# main.net
KiCad netlist of a schematic drawn in Altium Designer
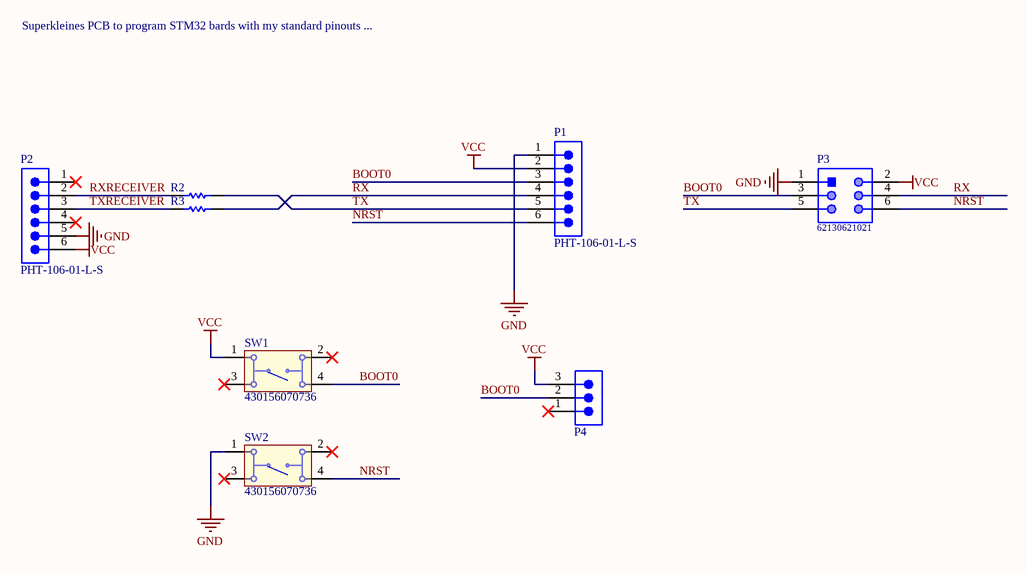
[diagram p0: main.SchDoc]

(export (version "E")
  (design (tool "Eeschema 10.0.6"))
  (components
    (comp (ref "P1")
      (value "PHT-106-01-L-S")
      (footprint "SMTC-PHT-106-01-X-S")
      (description "Press Fit Header, Through-hole, Vertical, -55 to 125 degC, 2.54 mm Pitch, 6-Pin, Male, RoHS")
      (fields (field (name "MANUFACTURER") "Samtec"))
      (libsource (lib "Altium Content Vault") (part "SMTC-PHT-106-01-X-S"))
    )
    (comp (ref "P2")
      (value "PHT-106-01-L-S")
      (footprint "SMTC-PHT-106-01-X-S")
      (description "Press Fit Header, Through-hole, Vertical, -55 to 125 degC, 2.54 mm Pitch, 6-Pin, Male, RoHS")
      (fields (field (name "MANUFACTURER") "Samtec"))
      (libsource (lib "Altium Content Vault") (part "SMTC-PHT-106-01-X-S"))
    )
    (comp (ref "P3")
      (value "62130621021")
      (footprint "62130621021")
      (description "SMT Vertical Pin Header WR-PHD, Pitch 1.27 mm, Dual Row, 6 pins")
      (fields (field (name "MANUFACTURER") "Wurth Elektronik") (field (name "PUBLISHER") "WurthElektronik"))
      (libsource (lib "Altium Content Vault") (part "WE-CN-2P-M-R6"))
    )
    (comp (ref "P4")
      (value "TSW-103-07-F-S")
      (footprint "SMTC-TSW-103-07-X-S")
      (fields (field (name "MANUFACTURER") "Samtec"))
      (libsource (lib "Altium Content Vault") (part "SMTC-TSW-103-X-X-S-X"))
    )
    (comp (ref "R2")
      (value "0")
      (footprint "RESC0805(2012)_L")
      (fields (field (name "TOLERANCE") "1 %") (field (name "POWER") "0.125 W"))
      (libsource (lib "Altium Content Vault") (part "RES"))
    )
    (comp (ref "R3")
      (value "0")
      (footprint "RESC0805(2012)_L")
      (fields (field (name "TOLERANCE") "1 %") (field (name "POWER") "0.125 W"))
      (libsource (lib "Altium Content Vault") (part "RES"))
    )
    (comp (ref "SW1")
      (value "430156070736")
      (footprint "430156070736")
      (description "WS-TATV THT Tact Switch 6X6 mm")
      (fields (field (name "MANUFACTURER") "Wuerth Elektronik"))
      (libsource (lib "Altium Content Vault") (part "WE-TACT-SW-4"))
    )
    (comp (ref "SW2")
      (value "430156070736")
      (footprint "430156070736")
      (description "WS-TATV THT Tact Switch 6X6 mm")
      (fields (field (name "MANUFACTURER") "Wuerth Elektronik"))
      (libsource (lib "Altium Content Vault") (part "WE-TACT-SW-4"))
    )
  )
  (nets
    (net (code "1") (name "/BOOT0") (class "Default")
      (node (ref "P1") (pin "3") (pinfunction "3_3") (pintype "passive"))
      (node (ref "P3") (pin "3") (pinfunction "3_3") (pintype "passive"))
      (node (ref "P4") (pin "2") (pinfunction "2_2") (pintype "passive"))
      (node (ref "SW1") (pin "4") (pinfunction "4_4") (pintype "passive"))
    )
    (net (code "2") (name "/NRST") (class "Default")
      (node (ref "P1") (pin "6") (pinfunction "6_6") (pintype "passive"))
      (node (ref "P3") (pin "6") (pinfunction "6_6") (pintype "passive"))
      (node (ref "SW2") (pin "4") (pinfunction "4_4") (pintype "passive"))
    )
    (net (code "3") (name "/RX") (class "Default")
      (node (ref "P1") (pin "4") (pinfunction "4_4") (pintype "passive"))
      (node (ref "P3") (pin "4") (pinfunction "4_4") (pintype "passive"))
      (node (ref "R3") (pin "1") (pinfunction "1_1") (pintype "passive"))
    )
    (net (code "4") (name "/RXRECEIVER") (class "Default")
      (node (ref "P2") (pin "2") (pinfunction "2_2") (pintype "passive"))
      (node (ref "R2") (pin "2") (pinfunction "2_2") (pintype "passive"))
    )
    (net (code "5") (name "/TX") (class "Default")
      (node (ref "P1") (pin "5") (pinfunction "5_5") (pintype "passive"))
      (node (ref "P3") (pin "5") (pinfunction "5_5") (pintype "passive"))
      (node (ref "R2") (pin "1") (pinfunction "1_1") (pintype "passive"))
    )
    (net (code "6") (name "/TXRECEIVER") (class "Default")
      (node (ref "P2") (pin "3") (pinfunction "3_3") (pintype "passive"))
      (node (ref "R3") (pin "2") (pinfunction "2_2") (pintype "passive"))
    )
    (net (code "7") (name "GND") (class "Default")
      (node (ref "P1") (pin "1") (pinfunction "1_1") (pintype "passive"))
      (node (ref "P2") (pin "5") (pinfunction "5_5") (pintype "passive"))
      (node (ref "P3") (pin "1") (pinfunction "1_1") (pintype "passive"))
      (node (ref "SW2") (pin "1") (pinfunction "1_1") (pintype "passive"))
    )
    (net (code "8") (name "VCC") (class "Default")
      (node (ref "P1") (pin "2") (pinfunction "2_2") (pintype "passive"))
      (node (ref "P2") (pin "6") (pinfunction "6_6") (pintype "passive"))
      (node (ref "P3") (pin "2") (pinfunction "2_2") (pintype "passive"))
      (node (ref "P4") (pin "3") (pinfunction "3_3") (pintype "passive"))
      (node (ref "SW1") (pin "1") (pinfunction "1_1") (pintype "passive"))
    )
    (net (code "9") (name "unconnected-(P2-Pad1)") (class "Default")
      (node (ref "P2") (pin "1") (pinfunction "1_1") (pintype "passive+no_connect"))
    )
    (net (code "10") (name "unconnected-(P2-Pad4)") (class "Default")
      (node (ref "P2") (pin "4") (pinfunction "4_4") (pintype "passive+no_connect"))
    )
    (net (code "11") (name "unconnected-(P4-Pad1)") (class "Default")
      (node (ref "P4") (pin "1") (pinfunction "1_1") (pintype "passive+no_connect"))
    )
    (net (code "12") (name "unconnected-(SW1-Pad2)") (class "Default")
      (node (ref "SW1") (pin "2") (pinfunction "2_2") (pintype "passive+no_connect"))
    )
    (net (code "13") (name "unconnected-(SW1-Pad3)") (class "Default")
      (node (ref "SW1") (pin "3") (pinfunction "3_3") (pintype "passive+no_connect"))
    )
    (net (code "14") (name "unconnected-(SW2-Pad2)") (class "Default")
      (node (ref "SW2") (pin "2") (pinfunction "2_2") (pintype "passive+no_connect"))
    )
    (net (code "15") (name "unconnected-(SW2-Pad3)") (class "Default")
      (node (ref "SW2") (pin "3") (pinfunction "3_3") (pintype "passive+no_connect"))
    )
  )
)
